# Adafruit_MiniPOV4_Kit.net
KiCad netlist of a schematic drawn in EAGLE
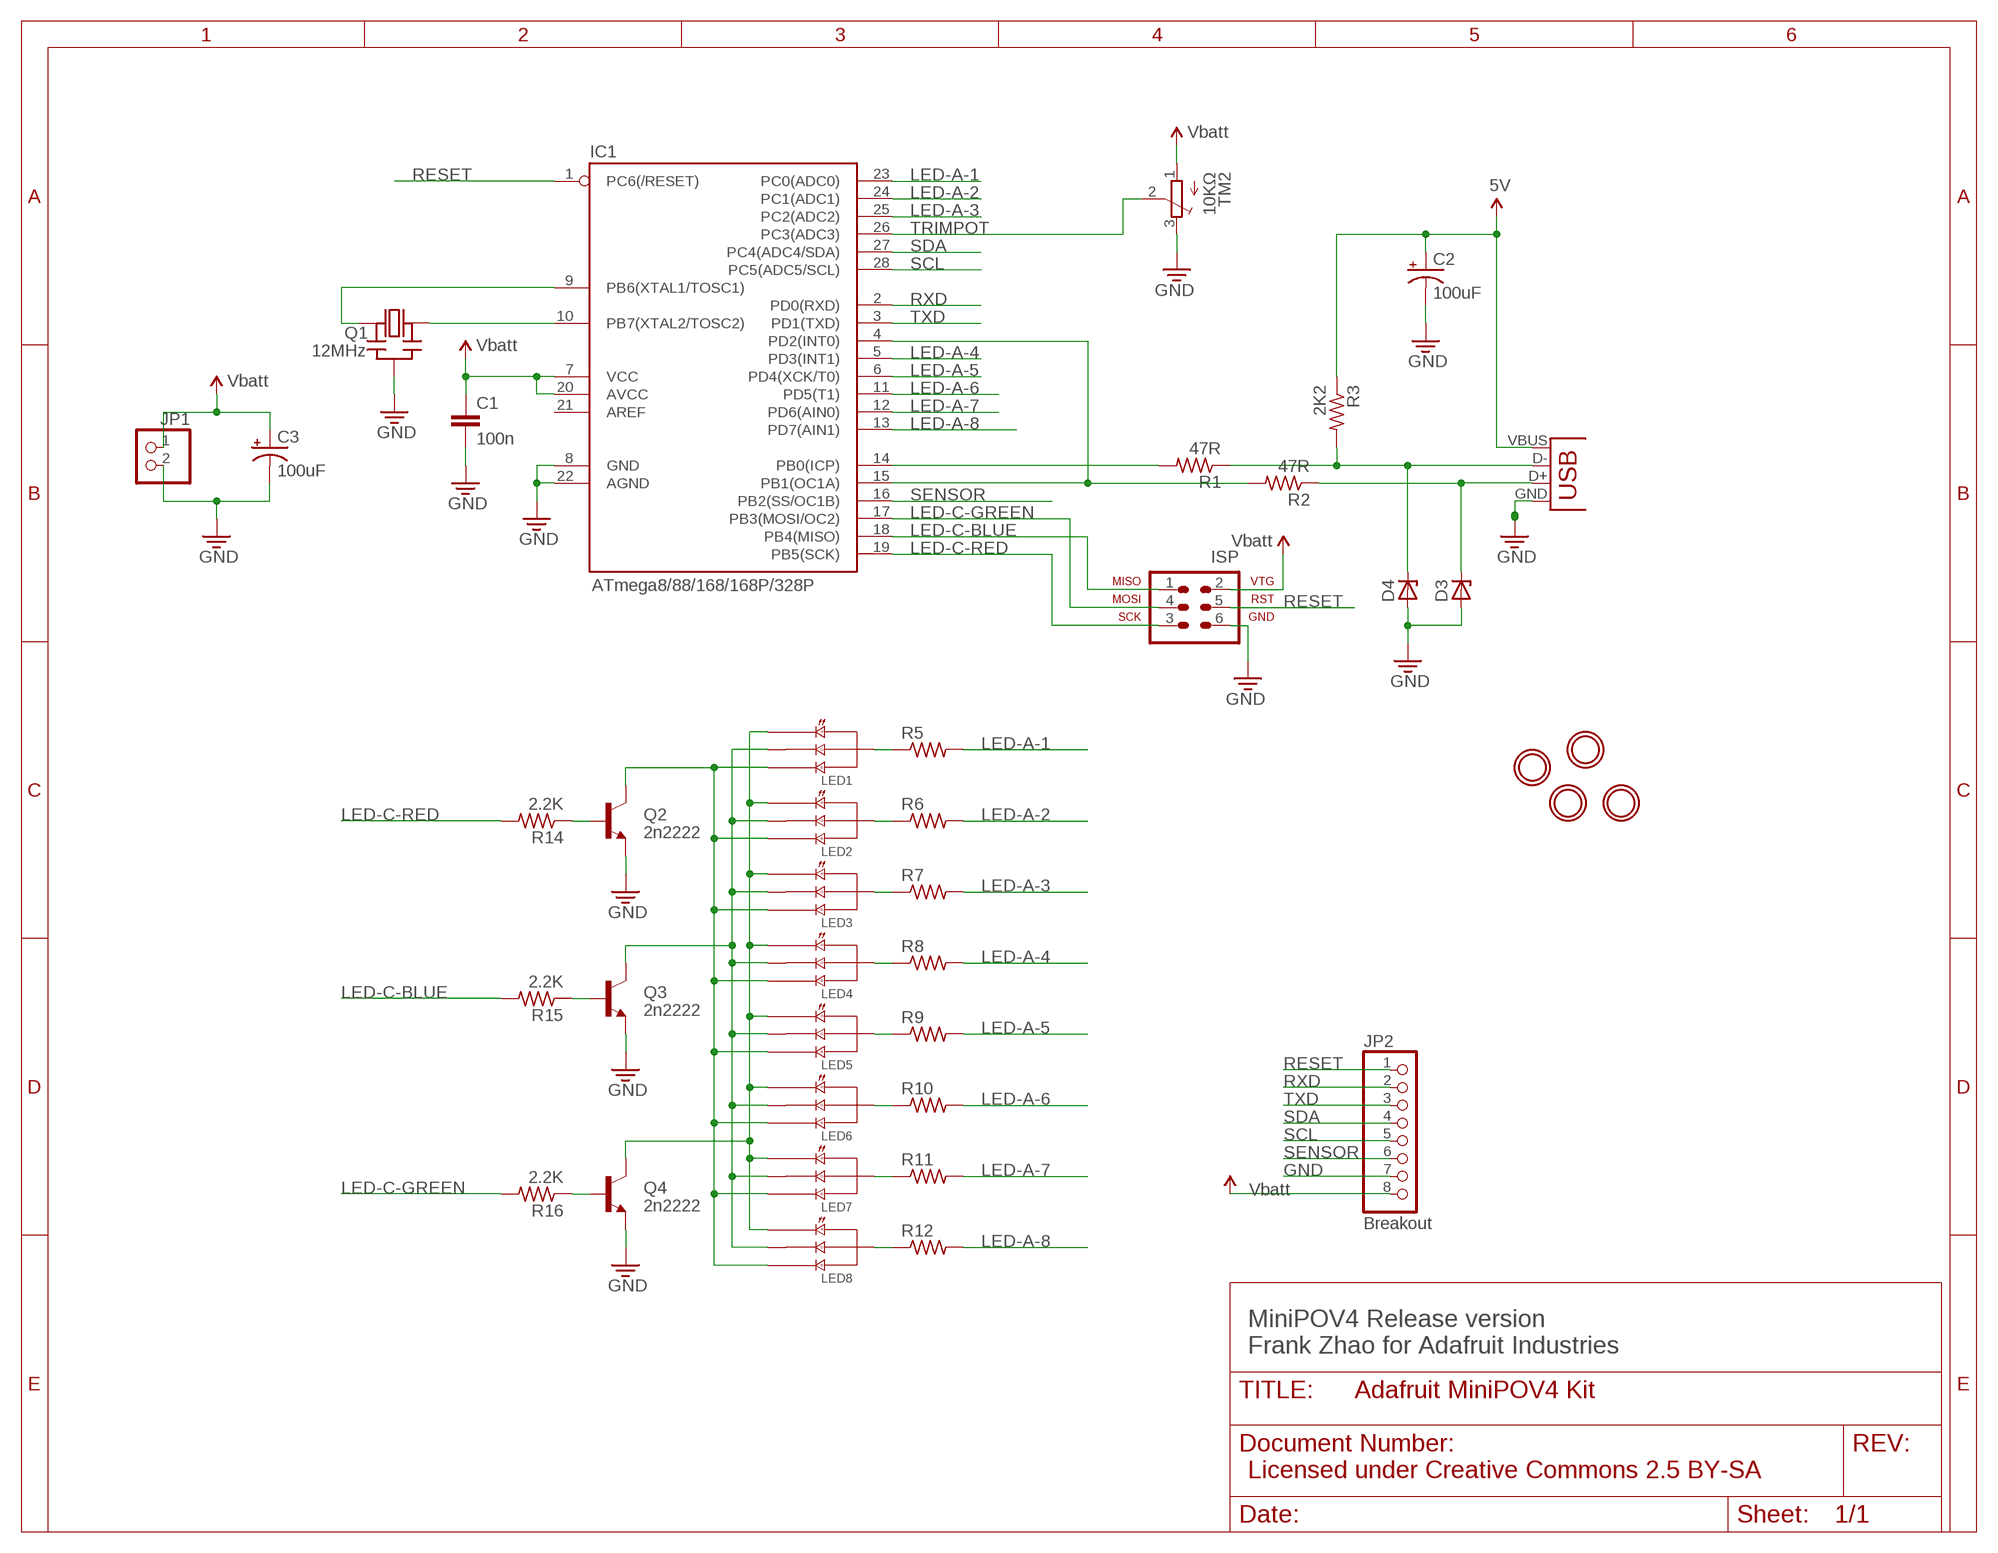
[diagram p0: schematic, sheet 1]

(export (version "E")
  (design (tool "Eeschema 10.0.6"))
  (components
    (comp (ref "C1")
      (value "100n")
      (footprint "eagle-import:CAP-PTH-SMALL2")
      (libsource (lib "eagle-import") (part "CAPPTH2"))
    )
    (comp (ref "C2")
      (value "100uF")
      (footprint "eagle-import:E2,5-6")
      (libsource (lib "eagle-import") (part "CPOL-USE2.5-6"))
    )
    (comp (ref "C3")
      (value "100uF")
      (footprint "eagle-import:E2,5-6")
      (libsource (lib "eagle-import") (part "CPOL-USE2.5-6"))
    )
    (comp (ref "D3")
      (value "ZENER-DIODEDO34-7")
      (footprint "eagle-import:DO34Z7")
      (libsource (lib "eagle-import") (part "ZENER-DIODEDO34-7"))
    )
    (comp (ref "D4")
      (value "ZENER-DIODEDO34-7")
      (footprint "eagle-import:DO34Z7")
      (libsource (lib "eagle-import") (part "ZENER-DIODEDO34-7"))
    )
    (comp (ref "IC1")
      (value "ATmega8/88/168/168P/328P")
      (footprint "eagle-import:DIL28-3")
      (libsource (lib "eagle-import") (part "AVR-MEGA8-PPTH"))
    )
    (comp (ref "ISP")
      (value "AVR-ISP-6")
      (footprint "eagle-import:AVR-ISP-6")
      (libsource (lib "eagle-import") (part "AVR-ISP-6"))
    )
    (comp (ref "JP1")
      (value "HEADER-1X2")
      (footprint "eagle-import:1X02_OVAL")
      (libsource (lib "eagle-import") (part "HEADER-1X2"))
    )
    (comp (ref "JP2")
      (value "Breakout")
      (footprint "eagle-import:1X08-BIG")
      (libsource (lib "eagle-import") (part "PINHD-1X8BIG"))
    )
    (comp (ref "LED1")
      (value "LED-RGB-CA-PIRANHA")
      (footprint "eagle-import:PIRANHA5MM")
      (libsource (lib "eagle-import") (part "LED-RGB-CA-PIRANHA"))
    )
    (comp (ref "LED2")
      (value "LED-RGB-CA-PIRANHA")
      (footprint "eagle-import:PIRANHA5MM")
      (libsource (lib "eagle-import") (part "LED-RGB-CA-PIRANHA"))
    )
    (comp (ref "LED3")
      (value "LED-RGB-CA-PIRANHA")
      (footprint "eagle-import:PIRANHA5MM")
      (libsource (lib "eagle-import") (part "LED-RGB-CA-PIRANHA"))
    )
    (comp (ref "LED4")
      (value "LED-RGB-CA-PIRANHA")
      (footprint "eagle-import:PIRANHA5MM")
      (libsource (lib "eagle-import") (part "LED-RGB-CA-PIRANHA"))
    )
    (comp (ref "LED5")
      (value "LED-RGB-CA-PIRANHA")
      (footprint "eagle-import:PIRANHA5MM")
      (libsource (lib "eagle-import") (part "LED-RGB-CA-PIRANHA"))
    )
    (comp (ref "LED6")
      (value "LED-RGB-CA-PIRANHA")
      (footprint "eagle-import:PIRANHA5MM")
      (libsource (lib "eagle-import") (part "LED-RGB-CA-PIRANHA"))
    )
    (comp (ref "LED7")
      (value "LED-RGB-CA-PIRANHA")
      (footprint "eagle-import:PIRANHA5MM")
      (libsource (lib "eagle-import") (part "LED-RGB-CA-PIRANHA"))
    )
    (comp (ref "LED8")
      (value "LED-RGB-CA-PIRANHA")
      (footprint "eagle-import:PIRANHA5MM")
      (libsource (lib "eagle-import") (part "LED-RGB-CA-PIRANHA"))
    )
    (comp (ref "Q1")
      (value "12MHz")
      (footprint "eagle-import:CERM_OSC")
      (libsource (lib "eagle-import") (part "CERMOSCILL"))
    )
    (comp (ref "Q2")
      (value "2n2222")
      (footprint "eagle-import:TO-92")
      (libsource (lib "eagle-import") (part "TRANSISTOR_NPNTO92"))
    )
    (comp (ref "Q3")
      (value "2n2222")
      (footprint "eagle-import:TO-92")
      (libsource (lib "eagle-import") (part "TRANSISTOR_NPNTO92"))
    )
    (comp (ref "Q4")
      (value "2n2222")
      (footprint "eagle-import:TO-92")
      (libsource (lib "eagle-import") (part "TRANSISTOR_NPNTO92"))
    )
    (comp (ref "R1")
      (value "47R")
      (footprint "eagle-import:0207_9")
      (libsource (lib "eagle-import") (part "R-US_0207/9"))
    )
    (comp (ref "R2")
      (value "47R")
      (footprint "eagle-import:0207_9")
      (libsource (lib "eagle-import") (part "R-US_0207/9"))
    )
    (comp (ref "R3")
      (value "2K2")
      (footprint "eagle-import:0207_9")
      (libsource (lib "eagle-import") (part "R-US_0207/9"))
    )
    (comp (ref "R5")
      (value "R-US_0207/9")
      (footprint "eagle-import:0207_9")
      (libsource (lib "eagle-import") (part "R-US_0207/9"))
    )
    (comp (ref "R6")
      (value "R-US_0207/9")
      (footprint "eagle-import:0207_9")
      (libsource (lib "eagle-import") (part "R-US_0207/9"))
    )
    (comp (ref "R7")
      (value "R-US_0207/9")
      (footprint "eagle-import:0207_9")
      (libsource (lib "eagle-import") (part "R-US_0207/9"))
    )
    (comp (ref "R8")
      (value "R-US_0207/9")
      (footprint "eagle-import:0207_9")
      (libsource (lib "eagle-import") (part "R-US_0207/9"))
    )
    (comp (ref "R9")
      (value "R-US_0207/9")
      (footprint "eagle-import:0207_9")
      (libsource (lib "eagle-import") (part "R-US_0207/9"))
    )
    (comp (ref "R10")
      (value "R-US_0207/9")
      (footprint "eagle-import:0207_9")
      (libsource (lib "eagle-import") (part "R-US_0207/9"))
    )
    (comp (ref "R11")
      (value "R-US_0207/9")
      (footprint "eagle-import:0207_9")
      (libsource (lib "eagle-import") (part "R-US_0207/9"))
    )
    (comp (ref "R12")
      (value "R-US_0207/9")
      (footprint "eagle-import:0207_9")
      (libsource (lib "eagle-import") (part "R-US_0207/9"))
    )
    (comp (ref "R14")
      (value "2.2K")
      (footprint "eagle-import:0207_9")
      (libsource (lib "eagle-import") (part "R-US_0207/9"))
    )
    (comp (ref "R15")
      (value "2.2K")
      (footprint "eagle-import:0207_9")
      (libsource (lib "eagle-import") (part "R-US_0207/9"))
    )
    (comp (ref "R16")
      (value "2.2K")
      (footprint "eagle-import:0207_9")
      (libsource (lib "eagle-import") (part "R-US_0207/9"))
    )
    (comp (ref "TM2")
      (value "10KΩ")
      (footprint "eagle-import:TRIM-3386")
      (libsource (lib "eagle-import") (part "TRIMPOT3386"))
    )
    (comp (ref "U$2")
      (value "MOUNTINGHOLE2.5_THICK")
      (footprint "eagle-import:MOUNTINGHOLE_2.5_PLATED_THICK")
      (libsource (lib "eagle-import") (part "MOUNTINGHOLE2.5_THICK"))
    )
    (comp (ref "U$3")
      (value "MOUNTINGHOLE2.5_THICK")
      (footprint "eagle-import:MOUNTINGHOLE_2.5_PLATED_THICK")
      (libsource (lib "eagle-import") (part "MOUNTINGHOLE2.5_THICK"))
    )
    (comp (ref "U$4")
      (value "MOUNTINGHOLE2.5_THICK")
      (footprint "eagle-import:MOUNTINGHOLE_2.5_PLATED_THICK")
      (libsource (lib "eagle-import") (part "MOUNTINGHOLE2.5_THICK"))
    )
    (comp (ref "U$5")
      (value "MOUNTINGHOLE2.5_THICK")
      (footprint "eagle-import:MOUNTINGHOLE_2.5_PLATED_THICK")
      (libsource (lib "eagle-import") (part "MOUNTINGHOLE2.5_THICK"))
    )
    (comp (ref "USB")
      (value "USBPTH")
      (footprint "eagle-import:USB-B-PTH")
      (libsource (lib "eagle-import") (part "USBPTH"))
    )
  )
  (nets
    (net (code "1") (name "/LED-A-1") (class "Default")
      (node (ref "IC1") (pin "23") (pinfunction "PC0(ADC0)_23") (pintype "bidirectional"))
      (node (ref "R5") (pin "2") (pinfunction "2_2") (pintype "passive"))
    )
    (net (code "2") (name "/LED-A-2") (class "Default")
      (node (ref "IC1") (pin "24") (pinfunction "PC1(ADC1)_24") (pintype "bidirectional"))
      (node (ref "R6") (pin "2") (pinfunction "2_2") (pintype "passive"))
    )
    (net (code "3") (name "/LED-A-3") (class "Default")
      (node (ref "IC1") (pin "25") (pinfunction "PC2(ADC2)_25") (pintype "bidirectional"))
      (node (ref "R7") (pin "2") (pinfunction "2_2") (pintype "passive"))
    )
    (net (code "4") (name "/LED-A-4") (class "Default")
      (node (ref "IC1") (pin "5") (pinfunction "PD3(INT1)_5") (pintype "bidirectional"))
      (node (ref "R8") (pin "2") (pinfunction "2_2") (pintype "passive"))
    )
    (net (code "5") (name "/LED-A-5") (class "Default")
      (node (ref "IC1") (pin "6") (pinfunction "PD4(XCK/T0)_6") (pintype "bidirectional"))
      (node (ref "R9") (pin "2") (pinfunction "2_2") (pintype "passive"))
    )
    (net (code "6") (name "/LED-A-6") (class "Default")
      (node (ref "IC1") (pin "11") (pinfunction "PD5(T1)_11") (pintype "bidirectional"))
      (node (ref "R10") (pin "2") (pinfunction "2_2") (pintype "passive"))
    )
    (net (code "7") (name "/LED-A-7") (class "Default")
      (node (ref "IC1") (pin "12") (pinfunction "PD6(AIN0)_12") (pintype "bidirectional"))
      (node (ref "R11") (pin "2") (pinfunction "2_2") (pintype "passive"))
    )
    (net (code "8") (name "/LED-A-8") (class "Default")
      (node (ref "IC1") (pin "13") (pinfunction "PD7(AIN1)_13") (pintype "bidirectional"))
      (node (ref "R12") (pin "2") (pinfunction "2_2") (pintype "passive"))
    )
    (net (code "9") (name "/LED-C-BLUE") (class "Default")
      (node (ref "IC1") (pin "18") (pinfunction "PB4(MISO)_18") (pintype "bidirectional"))
      (node (ref "ISP") (pin "1") (pinfunction "MISO_1") (pintype "passive"))
      (node (ref "R15") (pin "2") (pinfunction "2_2") (pintype "passive"))
    )
    (net (code "10") (name "/LED-C-GREEN") (class "Default")
      (node (ref "IC1") (pin "17") (pinfunction "PB3(MOSI/OC2)_17") (pintype "bidirectional"))
      (node (ref "ISP") (pin "4") (pinfunction "MOSI_4") (pintype "passive"))
      (node (ref "R16") (pin "2") (pinfunction "2_2") (pintype "passive"))
    )
    (net (code "11") (name "/LED-C-RED") (class "Default")
      (node (ref "IC1") (pin "19") (pinfunction "PB5(SCK)_19") (pintype "bidirectional"))
      (node (ref "ISP") (pin "3") (pinfunction "SCK_3") (pintype "passive"))
      (node (ref "R14") (pin "2") (pinfunction "2_2") (pintype "passive"))
    )
    (net (code "12") (name "/RESET") (class "Default")
      (node (ref "IC1") (pin "1") (pinfunction "PC6(/RESET)_1") (pintype "bidirectional"))
      (node (ref "ISP") (pin "5") (pinfunction "RST_5") (pintype "passive"))
      (node (ref "JP2") (pin "1") (pinfunction "1_1") (pintype "passive"))
    )
    (net (code "13") (name "/RXD") (class "Default")
      (node (ref "IC1") (pin "2") (pinfunction "PD0(RXD)_2") (pintype "bidirectional"))
      (node (ref "JP2") (pin "2") (pinfunction "2_2") (pintype "passive"))
    )
    (net (code "14") (name "/SCL") (class "Default")
      (node (ref "IC1") (pin "28") (pinfunction "PC5(ADC5/SCL)_28") (pintype "bidirectional"))
      (node (ref "JP2") (pin "5") (pinfunction "5_5") (pintype "passive"))
    )
    (net (code "15") (name "/SDA") (class "Default")
      (node (ref "IC1") (pin "27") (pinfunction "PC4(ADC4/SDA)_27") (pintype "bidirectional"))
      (node (ref "JP2") (pin "4") (pinfunction "4_4") (pintype "passive"))
    )
    (net (code "16") (name "/SENSOR") (class "Default")
      (node (ref "IC1") (pin "16") (pinfunction "PB2(SS/OC1B)_16") (pintype "bidirectional"))
      (node (ref "JP2") (pin "6") (pinfunction "6_6") (pintype "passive"))
    )
    (net (code "17") (name "/TRIMPOT") (class "Default")
      (node (ref "IC1") (pin "26") (pinfunction "PC3(ADC3)_26") (pintype "bidirectional"))
      (node (ref "TM2") (pin "2") (pinfunction "S_2") (pintype "passive"))
    )
    (net (code "18") (name "/TXD") (class "Default")
      (node (ref "IC1") (pin "3") (pinfunction "PD1(TXD)_3") (pintype "bidirectional"))
      (node (ref "JP2") (pin "3") (pinfunction "3_3") (pintype "passive"))
    )
    (net (code "19") (name "5V") (class "Default")
      (node (ref "C2") (pin "+") (pinfunction "+_+") (pintype "passive"))
      (node (ref "R3") (pin "1") (pinfunction "1_1") (pintype "passive"))
      (node (ref "USB") (pin "VBUS") (pinfunction "VBUS_VBUS") (pintype "bidirectional"))
    )
    (net (code "20") (name "GND") (class "Default")
      (node (ref "C1") (pin "2") (pinfunction "2_2") (pintype "passive"))
      (node (ref "C2") (pin "-") (pinfunction "-_-") (pintype "passive"))
      (node (ref "C3") (pin "-") (pinfunction "-_-") (pintype "passive"))
      (node (ref "D3") (pin "A") (pinfunction "A_A") (pintype "passive"))
      (node (ref "D4") (pin "A") (pinfunction "A_A") (pintype "passive"))
      (node (ref "IC1") (pin "22") (pinfunction "AGND_22") (pintype "bidirectional"))
      (node (ref "IC1") (pin "8") (pinfunction "GND_8") (pintype "bidirectional"))
      (node (ref "ISP") (pin "6") (pinfunction "GND_6") (pintype "passive"))
      (node (ref "JP1") (pin "2") (pinfunction "2_2") (pintype "passive"))
      (node (ref "JP2") (pin "7") (pinfunction "7_7") (pintype "passive"))
      (node (ref "Q1") (pin "G") (pinfunction "GND_G") (pintype "bidirectional"))
      (node (ref "Q2") (pin "1") (pinfunction "E_1") (pintype "passive"))
      (node (ref "Q3") (pin "1") (pinfunction "E_1") (pintype "passive"))
      (node (ref "Q4") (pin "1") (pinfunction "E_1") (pintype "passive"))
      (node (ref "TM2") (pin "3") (pinfunction "E_3") (pintype "passive"))
      (node (ref "USB") (pin "GND") (pinfunction "GND_GND") (pintype "bidirectional"))
      (node (ref "USB") (pin "S1") (pinfunction "P$1_S1") (pintype "bidirectional"))
      (node (ref "USB") (pin "S2") (pinfunction "P$1_S2") (pintype "bidirectional"))
    )
    (net (code "21") (name "Net-(D3-PadC)") (class "Default")
      (node (ref "D3") (pin "C") (pinfunction "C_C") (pintype "passive"))
      (node (ref "R2") (pin "1") (pinfunction "1_1") (pintype "passive"))
      (node (ref "USB") (pin "D+") (pinfunction "D+_D+") (pintype "bidirectional"))
    )
    (net (code "22") (name "Net-(D4-PadC)") (class "Default")
      (node (ref "D4") (pin "C") (pinfunction "C_C") (pintype "passive"))
      (node (ref "R1") (pin "1") (pinfunction "1_1") (pintype "passive"))
      (node (ref "R3") (pin "2") (pinfunction "2_2") (pintype "passive"))
      (node (ref "USB") (pin "D-") (pinfunction "D-_D-") (pintype "bidirectional"))
    )
    (net (code "23") (name "Net-(IC1-PB0(ICP))") (class "Default")
      (node (ref "IC1") (pin "14") (pinfunction "PB0(ICP)_14") (pintype "bidirectional"))
      (node (ref "R1") (pin "2") (pinfunction "2_2") (pintype "passive"))
    )
    (net (code "24") (name "Net-(IC1-PB1(OC1A))") (class "Default")
      (node (ref "IC1") (pin "15") (pinfunction "PB1(OC1A)_15") (pintype "bidirectional"))
      (node (ref "IC1") (pin "4") (pinfunction "PD2(INT0)_4") (pintype "bidirectional"))
      (node (ref "R2") (pin "2") (pinfunction "2_2") (pintype "passive"))
    )
    (net (code "25") (name "Net-(IC1-PB6(XTAL1{slash}TOSC1))") (class "Default")
      (node (ref "IC1") (pin "9") (pinfunction "PB6(XTAL1/TOSC1)_9") (pintype "bidirectional"))
      (node (ref "Q1") (pin "1") (pinfunction "IN_1") (pintype "bidirectional"))
    )
    (net (code "26") (name "Net-(IC1-PB7(XTAL2{slash}TOSC2))") (class "Default")
      (node (ref "IC1") (pin "10") (pinfunction "PB7(XTAL2/TOSC2)_10") (pintype "bidirectional"))
      (node (ref "Q1") (pin "2") (pinfunction "OUT_2") (pintype "bidirectional"))
    )
    (net (code "27") (name "Net-(LED1-B)") (class "Default")
      (node (ref "LED1") (pin "1") (pinfunction "B_1") (pintype "bidirectional"))
      (node (ref "LED2") (pin "1") (pinfunction "B_1") (pintype "bidirectional"))
      (node (ref "LED3") (pin "1") (pinfunction "B_1") (pintype "bidirectional"))
      (node (ref "LED4") (pin "1") (pinfunction "B_1") (pintype "bidirectional"))
      (node (ref "LED5") (pin "1") (pinfunction "B_1") (pintype "bidirectional"))
      (node (ref "LED6") (pin "1") (pinfunction "B_1") (pintype "bidirectional"))
      (node (ref "LED7") (pin "1") (pinfunction "B_1") (pintype "bidirectional"))
      (node (ref "LED8") (pin "1") (pinfunction "B_1") (pintype "bidirectional"))
      (node (ref "Q2") (pin "3") (pinfunction "C_3") (pintype "passive"))
    )
    (net (code "28") (name "Net-(LED1-C)") (class "Default")
      (node (ref "LED1") (pin "4") (pinfunction "C_4") (pintype "bidirectional"))
      (node (ref "R5") (pin "1") (pinfunction "1_1") (pintype "passive"))
    )
    (net (code "29") (name "Net-(LED1-G)") (class "Default")
      (node (ref "LED1") (pin "3") (pinfunction "G_3") (pintype "bidirectional"))
      (node (ref "LED2") (pin "3") (pinfunction "G_3") (pintype "bidirectional"))
      (node (ref "LED3") (pin "3") (pinfunction "G_3") (pintype "bidirectional"))
      (node (ref "LED4") (pin "3") (pinfunction "G_3") (pintype "bidirectional"))
      (node (ref "LED5") (pin "3") (pinfunction "G_3") (pintype "bidirectional"))
      (node (ref "LED6") (pin "3") (pinfunction "G_3") (pintype "bidirectional"))
      (node (ref "LED7") (pin "3") (pinfunction "G_3") (pintype "bidirectional"))
      (node (ref "LED8") (pin "3") (pinfunction "G_3") (pintype "bidirectional"))
      (node (ref "Q3") (pin "3") (pinfunction "C_3") (pintype "passive"))
    )
    (net (code "30") (name "Net-(LED1-R)") (class "Default")
      (node (ref "LED1") (pin "2") (pinfunction "R_2") (pintype "bidirectional"))
      (node (ref "LED2") (pin "2") (pinfunction "R_2") (pintype "bidirectional"))
      (node (ref "LED3") (pin "2") (pinfunction "R_2") (pintype "bidirectional"))
      (node (ref "LED4") (pin "2") (pinfunction "R_2") (pintype "bidirectional"))
      (node (ref "LED5") (pin "2") (pinfunction "R_2") (pintype "bidirectional"))
      (node (ref "LED6") (pin "2") (pinfunction "R_2") (pintype "bidirectional"))
      (node (ref "LED7") (pin "2") (pinfunction "R_2") (pintype "bidirectional"))
      (node (ref "LED8") (pin "2") (pinfunction "R_2") (pintype "bidirectional"))
      (node (ref "Q4") (pin "3") (pinfunction "C_3") (pintype "passive"))
    )
    (net (code "31") (name "Net-(LED2-C)") (class "Default")
      (node (ref "LED2") (pin "4") (pinfunction "C_4") (pintype "bidirectional"))
      (node (ref "R6") (pin "1") (pinfunction "1_1") (pintype "passive"))
    )
    (net (code "32") (name "Net-(LED3-C)") (class "Default")
      (node (ref "LED3") (pin "4") (pinfunction "C_4") (pintype "bidirectional"))
      (node (ref "R7") (pin "1") (pinfunction "1_1") (pintype "passive"))
    )
    (net (code "33") (name "Net-(LED4-C)") (class "Default")
      (node (ref "LED4") (pin "4") (pinfunction "C_4") (pintype "bidirectional"))
      (node (ref "R8") (pin "1") (pinfunction "1_1") (pintype "passive"))
    )
    (net (code "34") (name "Net-(LED5-C)") (class "Default")
      (node (ref "LED5") (pin "4") (pinfunction "C_4") (pintype "bidirectional"))
      (node (ref "R9") (pin "1") (pinfunction "1_1") (pintype "passive"))
    )
    (net (code "35") (name "Net-(LED6-C)") (class "Default")
      (node (ref "LED6") (pin "4") (pinfunction "C_4") (pintype "bidirectional"))
      (node (ref "R10") (pin "1") (pinfunction "1_1") (pintype "passive"))
    )
    (net (code "36") (name "Net-(LED7-C)") (class "Default")
      (node (ref "LED7") (pin "4") (pinfunction "C_4") (pintype "bidirectional"))
      (node (ref "R11") (pin "1") (pinfunction "1_1") (pintype "passive"))
    )
    (net (code "37") (name "Net-(LED8-C)") (class "Default")
      (node (ref "LED8") (pin "4") (pinfunction "C_4") (pintype "bidirectional"))
      (node (ref "R12") (pin "1") (pinfunction "1_1") (pintype "passive"))
    )
    (net (code "38") (name "Net-(Q2-B)") (class "Default")
      (node (ref "Q2") (pin "2") (pinfunction "B_2") (pintype "passive"))
      (node (ref "R14") (pin "1") (pinfunction "1_1") (pintype "passive"))
    )
    (net (code "39") (name "Net-(Q3-B)") (class "Default")
      (node (ref "Q3") (pin "2") (pinfunction "B_2") (pintype "passive"))
      (node (ref "R15") (pin "1") (pinfunction "1_1") (pintype "passive"))
    )
    (net (code "40") (name "Net-(Q4-B)") (class "Default")
      (node (ref "Q4") (pin "2") (pinfunction "B_2") (pintype "passive"))
      (node (ref "R16") (pin "1") (pinfunction "1_1") (pintype "passive"))
    )
    (net (code "41") (name "Vbatt") (class "Default")
      (node (ref "C1") (pin "1") (pinfunction "1_1") (pintype "passive"))
      (node (ref "C3") (pin "+") (pinfunction "+_+") (pintype "passive"))
      (node (ref "IC1") (pin "20") (pinfunction "AVCC_20") (pintype "bidirectional"))
      (node (ref "IC1") (pin "7") (pinfunction "VCC_7") (pintype "bidirectional"))
      (node (ref "ISP") (pin "2") (pinfunction "VTG_2") (pintype "passive"))
      (node (ref "JP1") (pin "1") (pinfunction "1_1") (pintype "passive"))
      (node (ref "JP2") (pin "8") (pinfunction "8_8") (pintype "passive"))
      (node (ref "TM2") (pin "1") (pinfunction "A_1") (pintype "passive"))
    )
    (net (code "42") (name "unconnected-(IC1-AREF-Pad21)") (class "Default")
      (node (ref "IC1") (pin "21") (pinfunction "AREF_21") (pintype "bidirectional"))
    )
  )
)
